# addon-candle-2.net
KiCad netlist of a schematic drawn in EAGLE
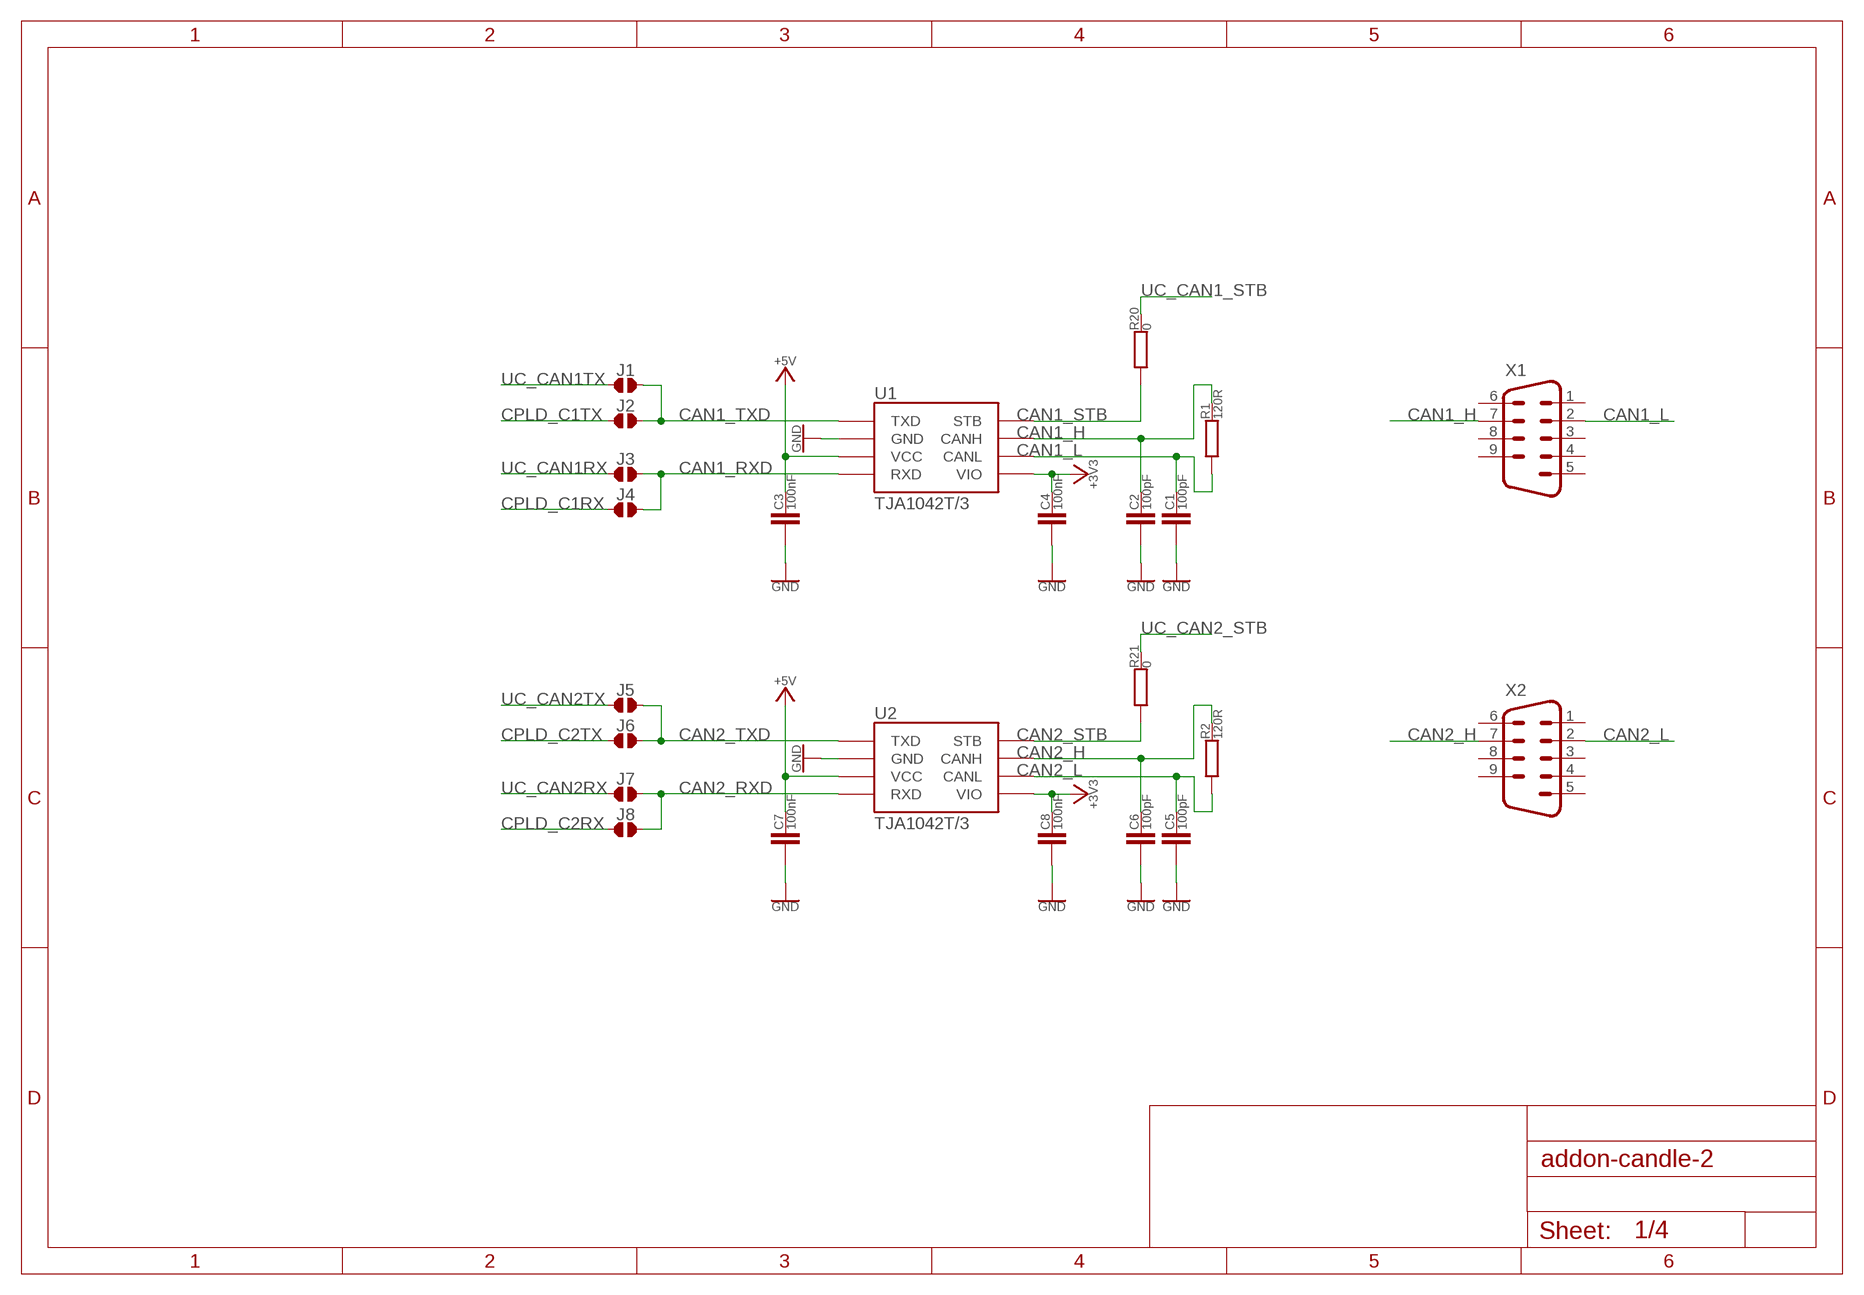
[diagram p0: schematic, sheet 1]
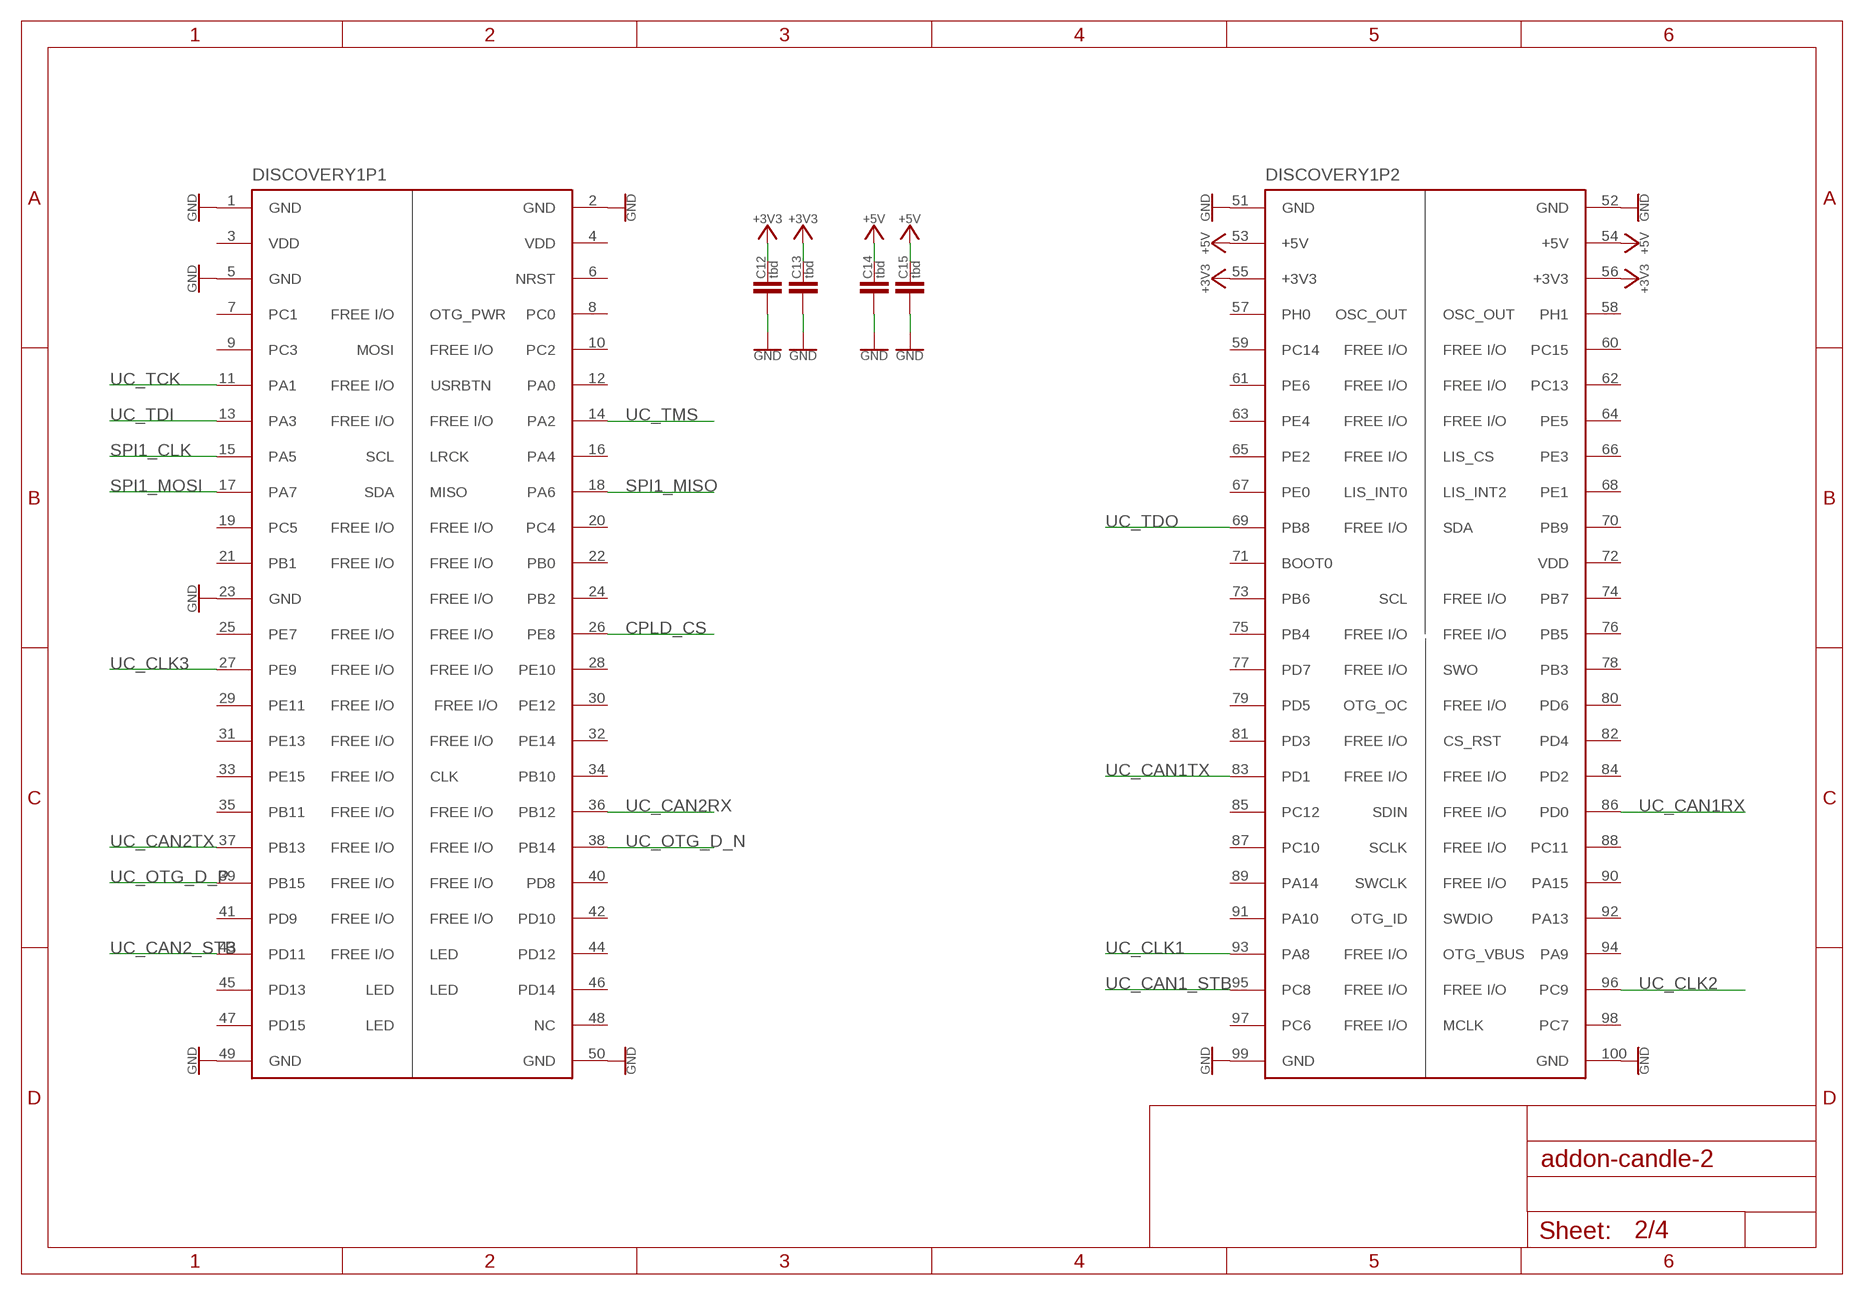
[diagram p1: schematic, sheet 2]
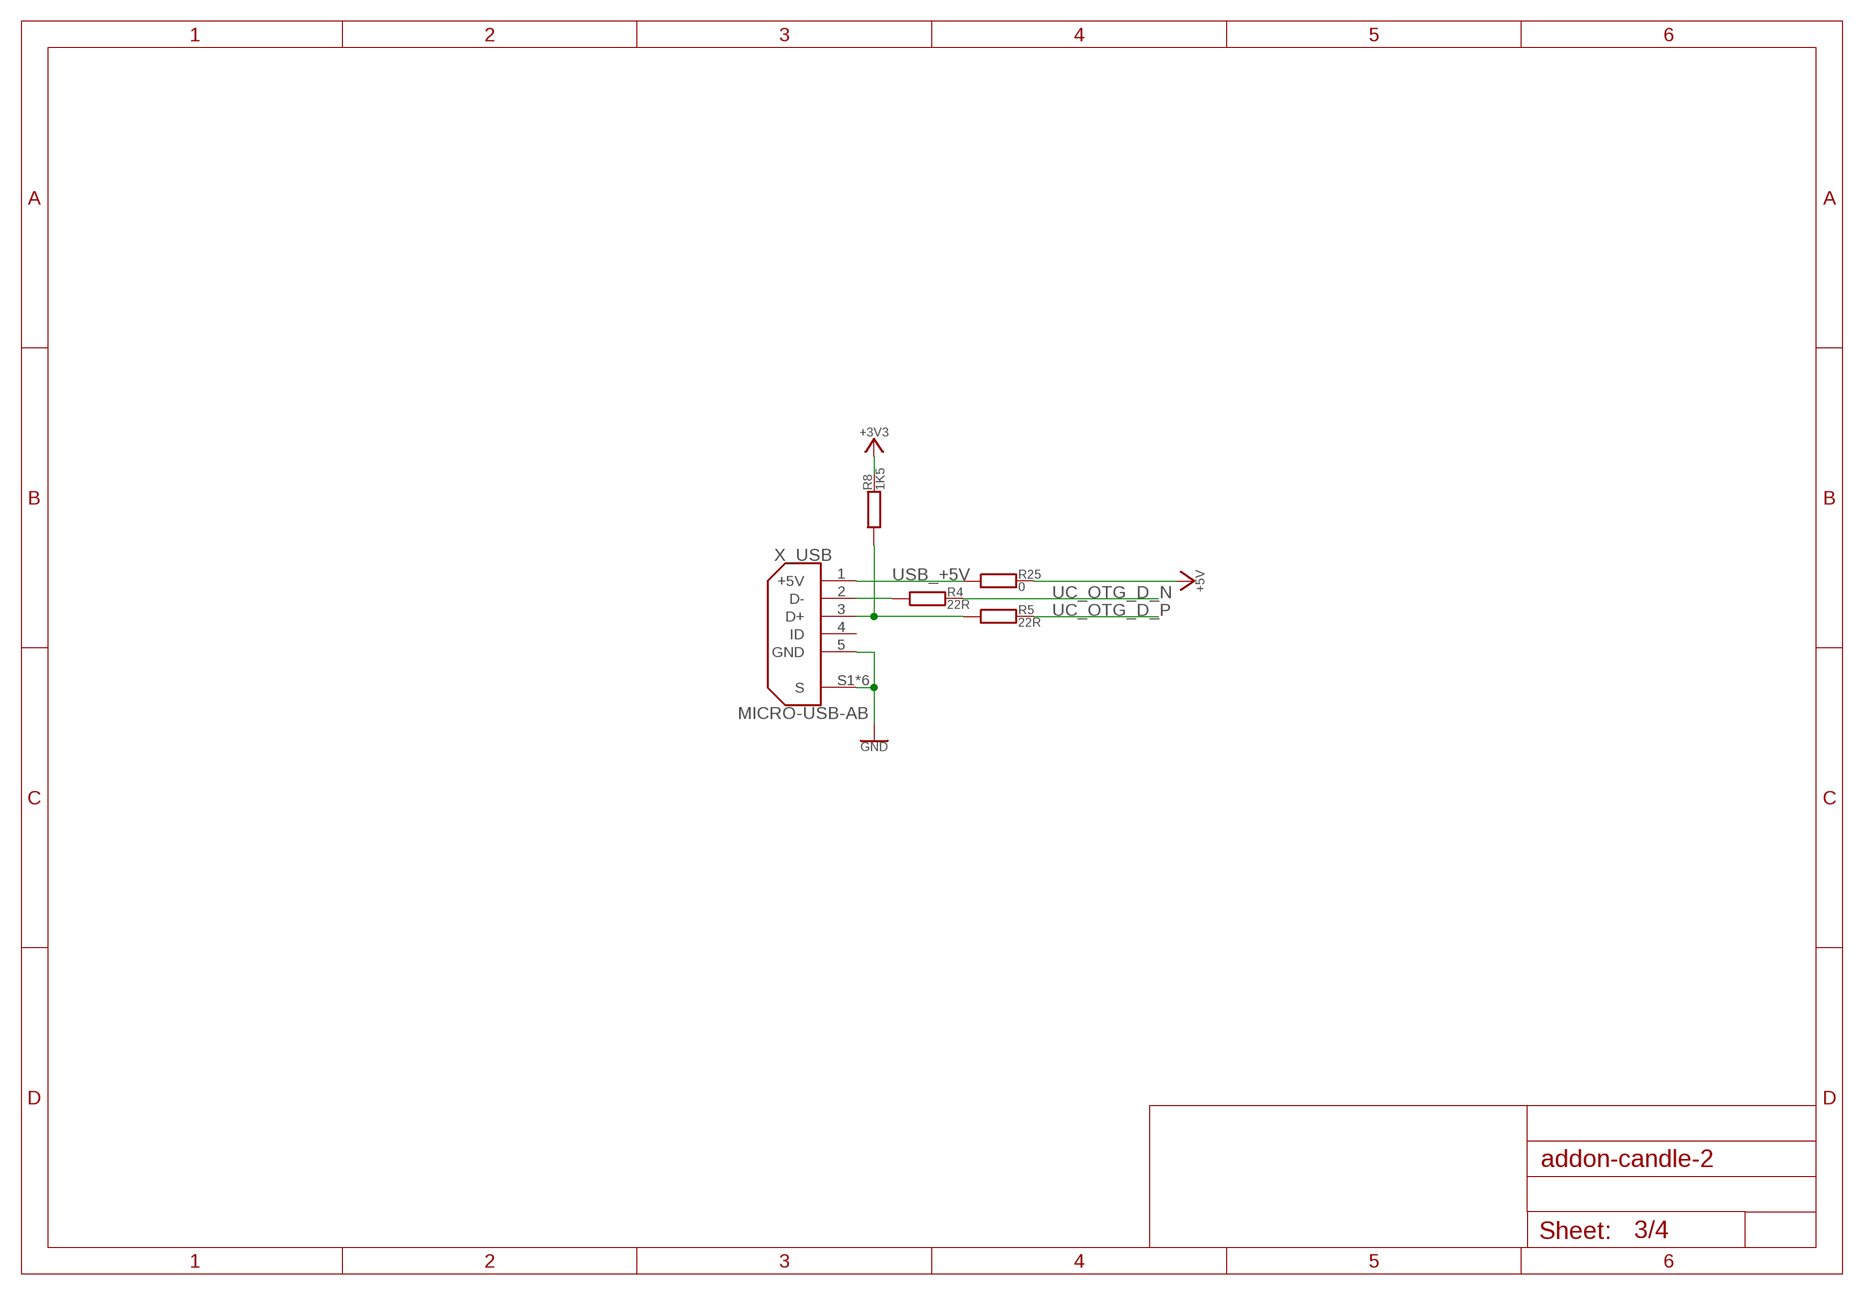
[diagram p2: schematic, sheet 3]
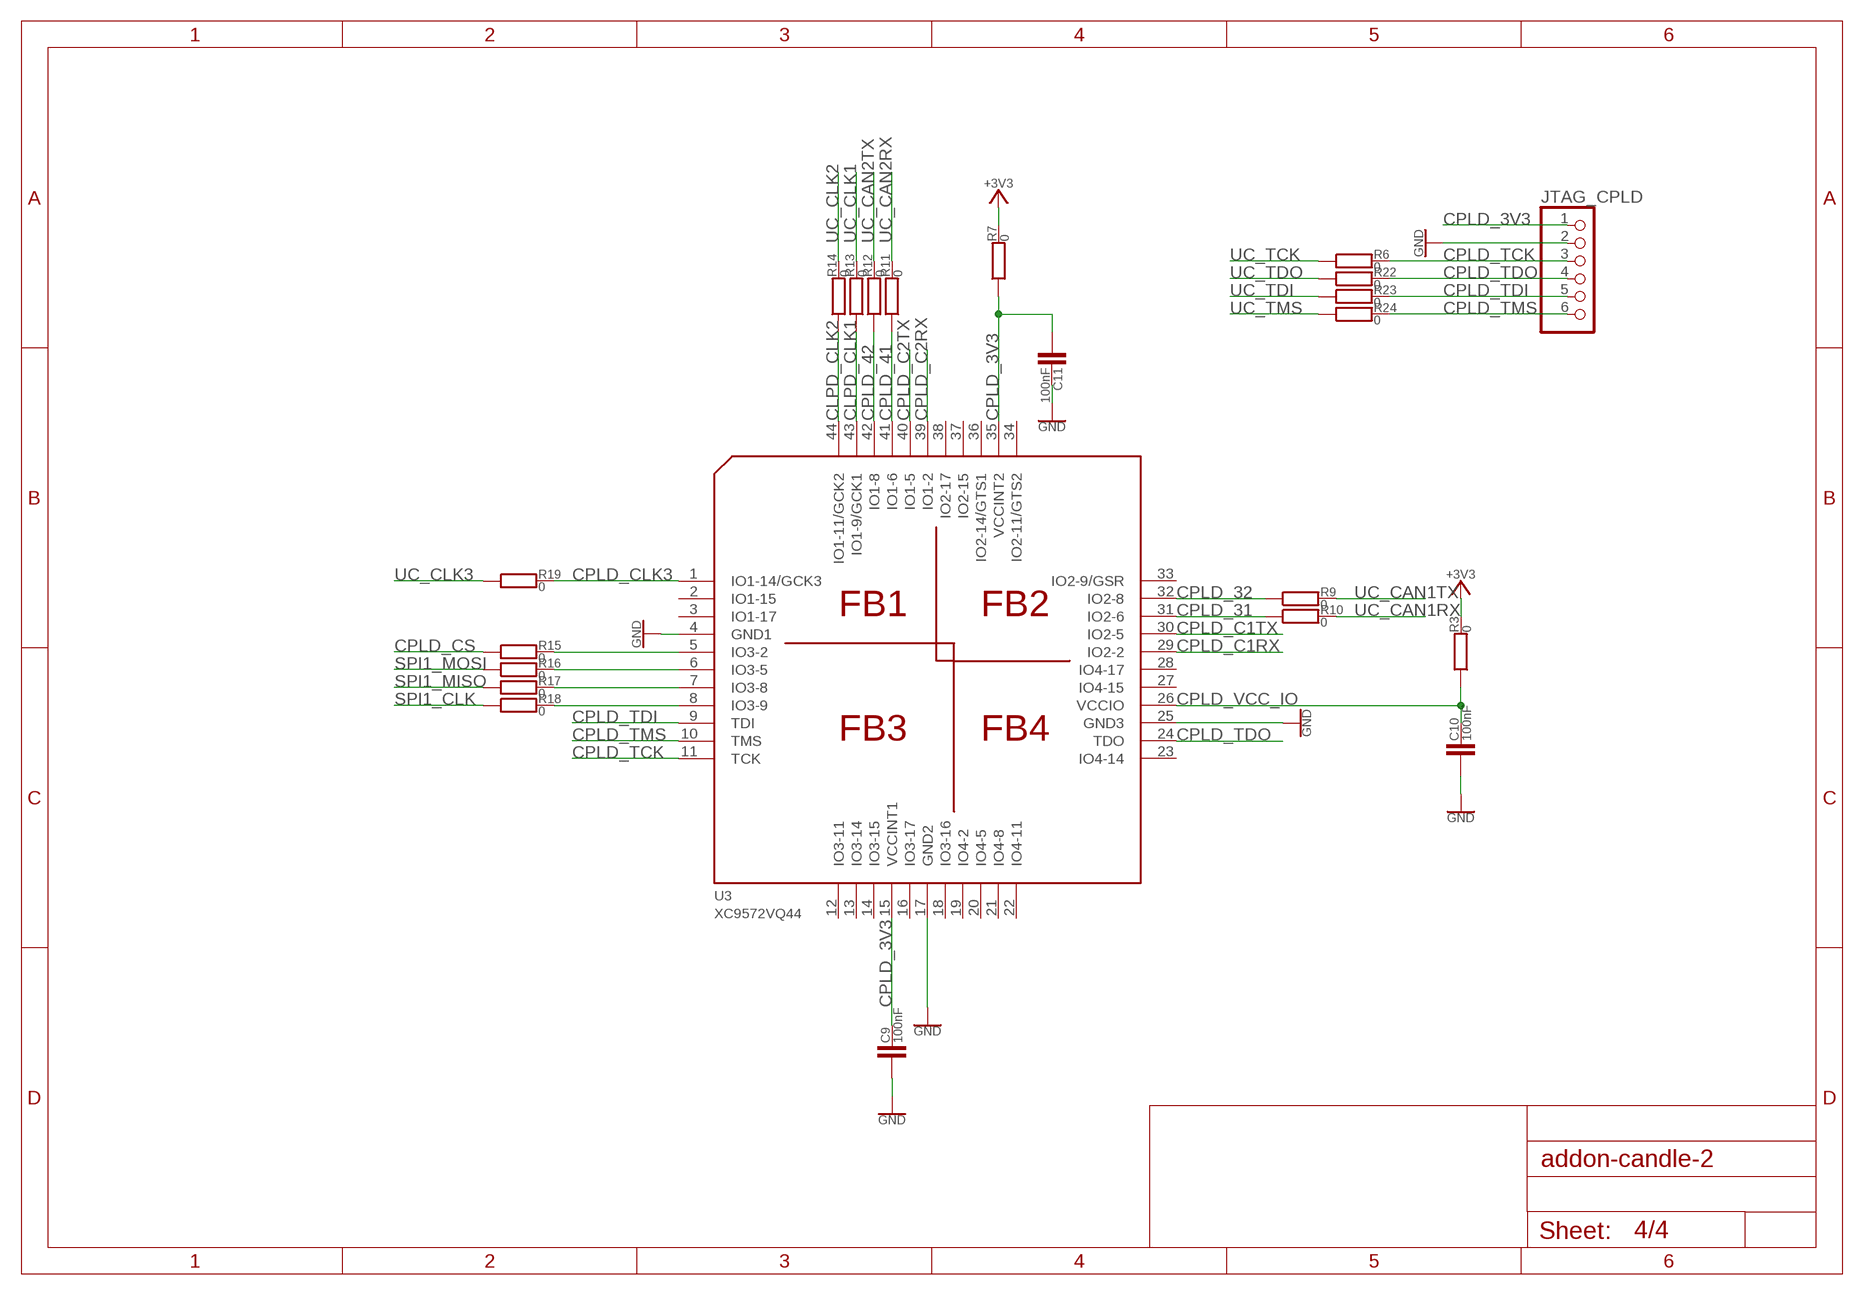
[diagram p3: schematic, sheet 4]

(export (version "E")
  (design (tool "Eeschema 10.0.6"))
  (components
    (comp (ref "C12")
      (value "tbd")
      (footprint "eagle-import:C1206")
      (libsource (lib "eagle-import") (part "C1206"))
    )
    (comp (ref "C13")
      (value "tbd")
      (footprint "eagle-import:C1206")
      (libsource (lib "eagle-import") (part "C1206"))
    )
    (comp (ref "C14")
      (value "tbd")
      (footprint "eagle-import:C1206")
      (libsource (lib "eagle-import") (part "C1206"))
    )
    (comp (ref "C15")
      (value "tbd")
      (footprint "eagle-import:C1206")
      (libsource (lib "eagle-import") (part "C1206"))
    )
    (comp (ref "DISCOVERY1")
      (value "STM32F4DISCOVERY")
      (footprint "eagle-import:STM32F4DISCOVERY")
      (libsource (lib "eagle-import") (part "STM32F4DISCOVERY"))
    )
    (comp (ref "C1")
      (value "100pF")
      (footprint "eagle-import:C0603")
      (libsource (lib "eagle-import") (part "C0603"))
    )
    (comp (ref "C2")
      (value "100pF")
      (footprint "eagle-import:C0603")
      (libsource (lib "eagle-import") (part "C0603"))
    )
    (comp (ref "C3")
      (value "100nF")
      (footprint "eagle-import:C0603")
      (libsource (lib "eagle-import") (part "C0603"))
    )
    (comp (ref "C4")
      (value "100nF")
      (footprint "eagle-import:C0603")
      (libsource (lib "eagle-import") (part "C0603"))
    )
    (comp (ref "C5")
      (value "100pF")
      (footprint "eagle-import:C0603")
      (libsource (lib "eagle-import") (part "C0603"))
    )
    (comp (ref "C6")
      (value "100pF")
      (footprint "eagle-import:C0603")
      (libsource (lib "eagle-import") (part "C0603"))
    )
    (comp (ref "C7")
      (value "100nF")
      (footprint "eagle-import:C0603")
      (libsource (lib "eagle-import") (part "C0603"))
    )
    (comp (ref "C8")
      (value "100nF")
      (footprint "eagle-import:C0603")
      (libsource (lib "eagle-import") (part "C0603"))
    )
    (comp (ref "J1")
      (value "JUMPER-2_10B")
      (footprint "eagle-import:JMP2-1B")
      (libsource (lib "eagle-import") (part "JUMPER-2_10B"))
    )
    (comp (ref "J2")
      (value "JUMPER-2_10B")
      (footprint "eagle-import:JMP2-1B")
      (libsource (lib "eagle-import") (part "JUMPER-2_10B"))
    )
    (comp (ref "J3")
      (value "JUMPER-2_10B")
      (footprint "eagle-import:JMP2-1B")
      (libsource (lib "eagle-import") (part "JUMPER-2_10B"))
    )
    (comp (ref "J4")
      (value "JUMPER-2_10B")
      (footprint "eagle-import:JMP2-1B")
      (libsource (lib "eagle-import") (part "JUMPER-2_10B"))
    )
    (comp (ref "J5")
      (value "JUMPER-2_10B")
      (footprint "eagle-import:JMP2-1B")
      (libsource (lib "eagle-import") (part "JUMPER-2_10B"))
    )
    (comp (ref "J6")
      (value "JUMPER-2_10B")
      (footprint "eagle-import:JMP2-1B")
      (libsource (lib "eagle-import") (part "JUMPER-2_10B"))
    )
    (comp (ref "J7")
      (value "JUMPER-2_10B")
      (footprint "eagle-import:JMP2-1B")
      (libsource (lib "eagle-import") (part "JUMPER-2_10B"))
    )
    (comp (ref "J8")
      (value "JUMPER-2_10B")
      (footprint "eagle-import:JMP2-1B")
      (libsource (lib "eagle-import") (part "JUMPER-2_10B"))
    )
    (comp (ref "R1")
      (value "120R")
      (footprint "eagle-import:R0603")
      (libsource (lib "eagle-import") (part "R0603"))
    )
    (comp (ref "R2")
      (value "120R")
      (footprint "eagle-import:R0603")
      (libsource (lib "eagle-import") (part "R0603"))
    )
    (comp (ref "R20")
      (value "0")
      (footprint "eagle-import:R0603")
      (libsource (lib "eagle-import") (part "R0603"))
    )
    (comp (ref "R21")
      (value "0")
      (footprint "eagle-import:R0603")
      (libsource (lib "eagle-import") (part "R0603"))
    )
    (comp (ref "U1")
      (value "TJA1042T/3")
      (footprint "eagle-import:SO08")
      (libsource (lib "eagle-import") (part "TJA1042T/3"))
    )
    (comp (ref "U2")
      (value "TJA1042T/3")
      (footprint "eagle-import:SO08")
      (libsource (lib "eagle-import") (part "TJA1042T/3"))
    )
    (comp (ref "X1")
      (value "M09-182")
      (footprint "eagle-import:182-009-MALE")
      (libsource (lib "eagle-import") (part "M09-182"))
    )
    (comp (ref "X2")
      (value "M09-182")
      (footprint "eagle-import:182-009-MALE")
      (libsource (lib "eagle-import") (part "M09-182"))
    )
    (comp (ref "C9")
      (value "100nF")
      (footprint "eagle-import:C0603")
      (libsource (lib "eagle-import") (part "C0603"))
    )
    (comp (ref "C10")
      (value "100nF")
      (footprint "eagle-import:C0603")
      (libsource (lib "eagle-import") (part "C0603"))
    )
    (comp (ref "C11")
      (value "100nF")
      (footprint "eagle-import:C0603")
      (libsource (lib "eagle-import") (part "C0603"))
    )
    (comp (ref "JTAG_CPLD")
      (value "PINHD-1X6")
      (footprint "eagle-import:1X06")
      (libsource (lib "eagle-import") (part "PINHD-1X6"))
    )
    (comp (ref "R3")
      (value "0")
      (footprint "eagle-import:R0603")
      (libsource (lib "eagle-import") (part "R0603"))
    )
    (comp (ref "R6")
      (value "0")
      (footprint "eagle-import:R0603")
      (libsource (lib "eagle-import") (part "R0603"))
    )
    (comp (ref "R7")
      (value "0")
      (footprint "eagle-import:R0603")
      (libsource (lib "eagle-import") (part "R0603"))
    )
    (comp (ref "R9")
      (value "0")
      (footprint "eagle-import:R0603")
      (libsource (lib "eagle-import") (part "R0603"))
    )
    (comp (ref "R10")
      (value "0")
      (footprint "eagle-import:R0603")
      (libsource (lib "eagle-import") (part "R0603"))
    )
    (comp (ref "R11")
      (value "0")
      (footprint "eagle-import:R0603")
      (libsource (lib "eagle-import") (part "R0603"))
    )
    (comp (ref "R12")
      (value "0")
      (footprint "eagle-import:R0603")
      (libsource (lib "eagle-import") (part "R0603"))
    )
    (comp (ref "R13")
      (value "0")
      (footprint "eagle-import:R0603")
      (libsource (lib "eagle-import") (part "R0603"))
    )
    (comp (ref "R14")
      (value "0")
      (footprint "eagle-import:R0603")
      (libsource (lib "eagle-import") (part "R0603"))
    )
    (comp (ref "R15")
      (value "0")
      (footprint "eagle-import:R0603")
      (libsource (lib "eagle-import") (part "R0603"))
    )
    (comp (ref "R16")
      (value "0")
      (footprint "eagle-import:R0603")
      (libsource (lib "eagle-import") (part "R0603"))
    )
    (comp (ref "R17")
      (value "0")
      (footprint "eagle-import:R0603")
      (libsource (lib "eagle-import") (part "R0603"))
    )
    (comp (ref "R18")
      (value "0")
      (footprint "eagle-import:R0603")
      (libsource (lib "eagle-import") (part "R0603"))
    )
    (comp (ref "R19")
      (value "0")
      (footprint "eagle-import:R0603")
      (libsource (lib "eagle-import") (part "R0603"))
    )
    (comp (ref "R22")
      (value "0")
      (footprint "eagle-import:R0603")
      (libsource (lib "eagle-import") (part "R0603"))
    )
    (comp (ref "R23")
      (value "0")
      (footprint "eagle-import:R0603")
      (libsource (lib "eagle-import") (part "R0603"))
    )
    (comp (ref "R24")
      (value "0")
      (footprint "eagle-import:R0603")
      (libsource (lib "eagle-import") (part "R0603"))
    )
    (comp (ref "U3")
      (value "XC9572VQ44")
      (footprint "eagle-import:VQ44")
      (libsource (lib "eagle-import") (part "XC9572VQ44"))
    )
    (comp (ref "R4")
      (value "22R")
      (footprint "eagle-import:R0603")
      (libsource (lib "eagle-import") (part "R0603"))
    )
    (comp (ref "R5")
      (value "22R")
      (footprint "eagle-import:R0603")
      (libsource (lib "eagle-import") (part "R0603"))
    )
    (comp (ref "R8")
      (value "1K5")
      (footprint "eagle-import:R0603")
      (libsource (lib "eagle-import") (part "R0603"))
    )
    (comp (ref "R25")
      (value "0")
      (footprint "eagle-import:R0603")
      (libsource (lib "eagle-import") (part "R0603"))
    )
    (comp (ref "X_USB")
      (value "MICRO-USB-AB")
      (footprint "eagle-import:ZX62-B-5PA(11)")
      (fields (field (name "MF") "HIROSE") (field (name "MPN") "ZX62-AB-5PA(11)"))
      (libsource (lib "eagle-import") (part "MICRO-USB-AB"))
    )
  )
  (nets
    (net (code "1") (name "+3V3") (class "Default")
      (node (ref "C12") (pin "2") (pinfunction "2_2") (pintype "passive"))
      (node (ref "C13") (pin "2") (pinfunction "2_2") (pintype "passive"))
      (node (ref "C4") (pin "2") (pinfunction "2_2") (pintype "passive"))
      (node (ref "C8") (pin "2") (pinfunction "2_2") (pintype "passive"))
      (node (ref "DISCOVERY1") (pin "55") (pinfunction "+3V3_55") (pintype "bidirectional"))
      (node (ref "DISCOVERY1") (pin "56") (pinfunction "+3V3_56") (pintype "bidirectional"))
      (node (ref "R3") (pin "2") (pinfunction "2_2") (pintype "passive"))
      (node (ref "R7") (pin "2") (pinfunction "2_2") (pintype "passive"))
      (node (ref "R8") (pin "2") (pinfunction "2_2") (pintype "passive"))
      (node (ref "U1") (pin "5") (pinfunction "VIO_5") (pintype "passive"))
      (node (ref "U2") (pin "5") (pinfunction "VIO_5") (pintype "passive"))
    )
    (net (code "2") (name "+5V") (class "Default")
      (node (ref "C14") (pin "2") (pinfunction "2_2") (pintype "passive"))
      (node (ref "C15") (pin "2") (pinfunction "2_2") (pintype "passive"))
      (node (ref "C3") (pin "2") (pinfunction "2_2") (pintype "passive"))
      (node (ref "C7") (pin "2") (pinfunction "2_2") (pintype "passive"))
      (node (ref "DISCOVERY1") (pin "53") (pinfunction "+5V_53") (pintype "bidirectional"))
      (node (ref "DISCOVERY1") (pin "54") (pinfunction "+5V_54") (pintype "bidirectional"))
      (node (ref "R25") (pin "2") (pinfunction "2_2") (pintype "passive"))
      (node (ref "U1") (pin "3") (pinfunction "VCC_3") (pintype "power_in"))
      (node (ref "U2") (pin "3") (pinfunction "VCC_3") (pintype "power_in"))
    )
    (net (code "3") (name "CAN1_H") (class "Default")
      (node (ref "C2") (pin "2") (pinfunction "2_2") (pintype "passive"))
      (node (ref "R1") (pin "2") (pinfunction "2_2") (pintype "passive"))
      (node (ref "U1") (pin "7") (pinfunction "CANH_7") (pintype "passive"))
      (node (ref "X1") (pin "7") (pinfunction "7_7") (pintype "passive"))
    )
    (net (code "4") (name "CAN1_L") (class "Default")
      (node (ref "C1") (pin "2") (pinfunction "2_2") (pintype "passive"))
      (node (ref "R1") (pin "1") (pinfunction "1_1") (pintype "passive"))
      (node (ref "U1") (pin "6") (pinfunction "CANL_6") (pintype "passive"))
      (node (ref "X1") (pin "2") (pinfunction "2_2") (pintype "passive"))
    )
    (net (code "5") (name "CAN1_RXD") (class "Default")
      (node (ref "J3") (pin "1") (pinfunction "1_1") (pintype "passive"))
      (node (ref "J4") (pin "1") (pinfunction "1_1") (pintype "passive"))
      (node (ref "U1") (pin "4") (pinfunction "RXD_4") (pintype "output"))
    )
    (net (code "6") (name "CAN1_STB") (class "Default")
      (node (ref "R20") (pin "1") (pinfunction "1_1") (pintype "passive"))
      (node (ref "U1") (pin "8") (pinfunction "STB_8") (pintype "input"))
    )
    (net (code "7") (name "CAN1_TXD") (class "Default")
      (node (ref "J1") (pin "1") (pinfunction "1_1") (pintype "passive"))
      (node (ref "J2") (pin "1") (pinfunction "1_1") (pintype "passive"))
      (node (ref "U1") (pin "1") (pinfunction "TXD_1") (pintype "input"))
    )
    (net (code "8") (name "CAN2_H") (class "Default")
      (node (ref "C6") (pin "2") (pinfunction "2_2") (pintype "passive"))
      (node (ref "R2") (pin "2") (pinfunction "2_2") (pintype "passive"))
      (node (ref "U2") (pin "7") (pinfunction "CANH_7") (pintype "passive"))
      (node (ref "X2") (pin "7") (pinfunction "7_7") (pintype "passive"))
    )
    (net (code "9") (name "CAN2_L") (class "Default")
      (node (ref "C5") (pin "2") (pinfunction "2_2") (pintype "passive"))
      (node (ref "R2") (pin "1") (pinfunction "1_1") (pintype "passive"))
      (node (ref "U2") (pin "6") (pinfunction "CANL_6") (pintype "passive"))
      (node (ref "X2") (pin "2") (pinfunction "2_2") (pintype "passive"))
    )
    (net (code "10") (name "CAN2_RXD") (class "Default")
      (node (ref "J7") (pin "1") (pinfunction "1_1") (pintype "passive"))
      (node (ref "J8") (pin "1") (pinfunction "1_1") (pintype "passive"))
      (node (ref "U2") (pin "4") (pinfunction "RXD_4") (pintype "output"))
    )
    (net (code "11") (name "CAN2_STB") (class "Default")
      (node (ref "R21") (pin "1") (pinfunction "1_1") (pintype "passive"))
      (node (ref "U2") (pin "8") (pinfunction "STB_8") (pintype "input"))
    )
    (net (code "12") (name "CAN2_TXD") (class "Default")
      (node (ref "J5") (pin "1") (pinfunction "1_1") (pintype "passive"))
      (node (ref "J6") (pin "1") (pinfunction "1_1") (pintype "passive"))
      (node (ref "U2") (pin "1") (pinfunction "TXD_1") (pintype "input"))
    )
    (net (code "13") (name "CLPD_CLK1") (class "Default")
      (node (ref "R13") (pin "1") (pinfunction "1_1") (pintype "passive"))
      (node (ref "U3") (pin "43") (pinfunction "IO1-9/GCK1_43") (pintype "bidirectional"))
    )
    (net (code "14") (name "CLPD_CLK2") (class "Default")
      (node (ref "R14") (pin "1") (pinfunction "1_1") (pintype "passive"))
      (node (ref "U3") (pin "44") (pinfunction "IO1-11/GCK2_44") (pintype "bidirectional"))
    )
    (net (code "15") (name "CPLD_3V3") (class "Default")
      (node (ref "C11") (pin "1") (pinfunction "1_1") (pintype "passive"))
      (node (ref "C9") (pin "2") (pinfunction "2_2") (pintype "passive"))
      (node (ref "JTAG_CPLD") (pin "1") (pinfunction "1_1") (pintype "passive"))
      (node (ref "R7") (pin "1") (pinfunction "1_1") (pintype "passive"))
      (node (ref "U3") (pin "15") (pinfunction "VCCINT1_15") (pintype "bidirectional"))
      (node (ref "U3") (pin "35") (pinfunction "VCCINT2_35") (pintype "bidirectional"))
    )
    (net (code "16") (name "CPLD_31") (class "Default")
      (node (ref "R10") (pin "1") (pinfunction "1_1") (pintype "passive"))
      (node (ref "U3") (pin "31") (pinfunction "IO2-6_31") (pintype "bidirectional"))
    )
    (net (code "17") (name "CPLD_32") (class "Default")
      (node (ref "R9") (pin "1") (pinfunction "1_1") (pintype "passive"))
      (node (ref "U3") (pin "32") (pinfunction "IO2-8_32") (pintype "bidirectional"))
    )
    (net (code "18") (name "CPLD_41") (class "Default")
      (node (ref "R11") (pin "1") (pinfunction "1_1") (pintype "passive"))
      (node (ref "U3") (pin "41") (pinfunction "IO1-6_41") (pintype "bidirectional"))
    )
    (net (code "19") (name "CPLD_42") (class "Default")
      (node (ref "R12") (pin "1") (pinfunction "1_1") (pintype "passive"))
      (node (ref "U3") (pin "42") (pinfunction "IO1-8_42") (pintype "bidirectional"))
    )
    (net (code "20") (name "CPLD_C1RX") (class "Default")
      (node (ref "J4") (pin "2") (pinfunction "2_2") (pintype "passive"))
      (node (ref "U3") (pin "29") (pinfunction "IO2-2_29") (pintype "bidirectional"))
    )
    (net (code "21") (name "CPLD_C1TX") (class "Default")
      (node (ref "J2") (pin "2") (pinfunction "2_2") (pintype "passive"))
      (node (ref "U3") (pin "30") (pinfunction "IO2-5_30") (pintype "bidirectional"))
    )
    (net (code "22") (name "CPLD_C2RX") (class "Default")
      (node (ref "J8") (pin "2") (pinfunction "2_2") (pintype "passive"))
      (node (ref "U3") (pin "39") (pinfunction "IO1-2_39") (pintype "bidirectional"))
    )
    (net (code "23") (name "CPLD_C2TX") (class "Default")
      (node (ref "J6") (pin "2") (pinfunction "2_2") (pintype "passive"))
      (node (ref "U3") (pin "40") (pinfunction "IO1-5_40") (pintype "bidirectional"))
    )
    (net (code "24") (name "CPLD_CLK3") (class "Default")
      (node (ref "R19") (pin "2") (pinfunction "2_2") (pintype "passive"))
      (node (ref "U3") (pin "1") (pinfunction "IO1-14/GCK3_1") (pintype "bidirectional"))
    )
    (net (code "25") (name "CPLD_CS") (class "Default")
      (node (ref "DISCOVERY1") (pin "26") (pinfunction "PE8_26") (pintype "bidirectional"))
      (node (ref "R15") (pin "1") (pinfunction "1_1") (pintype "passive"))
    )
    (net (code "26") (name "CPLD_TCK") (class "Default")
      (node (ref "JTAG_CPLD") (pin "3") (pinfunction "3_3") (pintype "passive"))
      (node (ref "R6") (pin "2") (pinfunction "2_2") (pintype "passive"))
      (node (ref "U3") (pin "11") (pinfunction "TCK_11") (pintype "bidirectional"))
    )
    (net (code "27") (name "CPLD_TDI") (class "Default")
      (node (ref "JTAG_CPLD") (pin "5") (pinfunction "5_5") (pintype "passive"))
      (node (ref "R23") (pin "2") (pinfunction "2_2") (pintype "passive"))
      (node (ref "U3") (pin "9") (pinfunction "TDI_9") (pintype "bidirectional"))
    )
    (net (code "28") (name "CPLD_TDO") (class "Default")
      (node (ref "JTAG_CPLD") (pin "4") (pinfunction "4_4") (pintype "passive"))
      (node (ref "R22") (pin "2") (pinfunction "2_2") (pintype "passive"))
      (node (ref "U3") (pin "24") (pinfunction "TDO_24") (pintype "bidirectional"))
    )
    (net (code "29") (name "CPLD_TMS") (class "Default")
      (node (ref "JTAG_CPLD") (pin "6") (pinfunction "6_6") (pintype "passive"))
      (node (ref "R24") (pin "2") (pinfunction "2_2") (pintype "passive"))
      (node (ref "U3") (pin "10") (pinfunction "TMS_10") (pintype "bidirectional"))
    )
    (net (code "30") (name "CPLD_VCC_IO") (class "Default")
      (node (ref "C10") (pin "2") (pinfunction "2_2") (pintype "passive"))
      (node (ref "R3") (pin "1") (pinfunction "1_1") (pintype "passive"))
      (node (ref "U3") (pin "26") (pinfunction "VCCIO_26") (pintype "bidirectional"))
    )
    (net (code "31") (name "GND") (class "Default")
      (node (ref "C1") (pin "1") (pinfunction "1_1") (pintype "passive"))
      (node (ref "C10") (pin "1") (pinfunction "1_1") (pintype "passive"))
      (node (ref "C11") (pin "2") (pinfunction "2_2") (pintype "passive"))
      (node (ref "C12") (pin "1") (pinfunction "1_1") (pintype "passive"))
      (node (ref "C13") (pin "1") (pinfunction "1_1") (pintype "passive"))
      (node (ref "C14") (pin "1") (pinfunction "1_1") (pintype "passive"))
      (node (ref "C15") (pin "1") (pinfunction "1_1") (pintype "passive"))
      (node (ref "C2") (pin "1") (pinfunction "1_1") (pintype "passive"))
      (node (ref "C3") (pin "1") (pinfunction "1_1") (pintype "passive"))
      (node (ref "C4") (pin "1") (pinfunction "1_1") (pintype "passive"))
      (node (ref "C5") (pin "1") (pinfunction "1_1") (pintype "passive"))
      (node (ref "C6") (pin "1") (pinfunction "1_1") (pintype "passive"))
      (node (ref "C7") (pin "1") (pinfunction "1_1") (pintype "passive"))
      (node (ref "C8") (pin "1") (pinfunction "1_1") (pintype "passive"))
      (node (ref "C9") (pin "1") (pinfunction "1_1") (pintype "passive"))
      (node (ref "DISCOVERY1") (pin "1") (pinfunction "GND_1") (pintype "bidirectional"))
      (node (ref "DISCOVERY1") (pin "100") (pinfunction "GND_100") (pintype "bidirectional"))
      (node (ref "DISCOVERY1") (pin "2") (pinfunction "GND_2") (pintype "bidirectional"))
      (node (ref "DISCOVERY1") (pin "23") (pinfunction "GND_23") (pintype "bidirectional"))
      (node (ref "DISCOVERY1") (pin "49") (pinfunction "GND_49") (pintype "bidirectional"))
      (node (ref "DISCOVERY1") (pin "5") (pinfunction "GND_5") (pintype "bidirectional"))
      (node (ref "DISCOVERY1") (pin "50") (pinfunction "GND_50") (pintype "bidirectional"))
      (node (ref "DISCOVERY1") (pin "51") (pinfunction "GND_51") (pintype "bidirectional"))
      (node (ref "DISCOVERY1") (pin "52") (pinfunction "GND_52") (pintype "bidirectional"))
      (node (ref "DISCOVERY1") (pin "99") (pinfunction "GND_99") (pintype "bidirectional"))
      (node (ref "JTAG_CPLD") (pin "2") (pinfunction "2_2") (pintype "passive"))
      (node (ref "U1") (pin "2") (pinfunction "GND_2") (pintype "power_in"))
      (node (ref "U2") (pin "2") (pinfunction "GND_2") (pintype "power_in"))
      (node (ref "U3") (pin "17") (pinfunction "GND2_17") (pintype "bidirectional"))
      (node (ref "U3") (pin "25") (pinfunction "GND3_25") (pintype "bidirectional"))
      (node (ref "U3") (pin "4") (pinfunction "GND1_4") (pintype "bidirectional"))
      (node (ref "X_USB") (pin "5") (pinfunction "GND_5") (pintype "passive"))
      (node (ref "X_USB") (pin "S1") (pinfunction "S_S1") (pintype "passive"))
      (node (ref "X_USB") (pin "S2") (pinfunction "S_S2") (pintype "passive"))
      (node (ref "X_USB") (pin "S3") (pinfunction "S_S3") (pintype "passive"))
      (node (ref "X_USB") (pin "S4") (pinfunction "S_S4") (pintype "passive"))
      (node (ref "X_USB") (pin "S5") (pinfunction "S_S5") (pintype "passive"))
      (node (ref "X_USB") (pin "S6") (pinfunction "S_S6") (pintype "passive"))
    )
    (net (code "32") (name "Net-(U3-IO3-2)") (class "Default")
      (node (ref "R15") (pin "2") (pinfunction "2_2") (pintype "passive"))
      (node (ref "U3") (pin "5") (pinfunction "IO3-2_5") (pintype "bidirectional"))
    )
    (net (code "33") (name "Net-(U3-IO3-5)") (class "Default")
      (node (ref "R16") (pin "2") (pinfunction "2_2") (pintype "passive"))
      (node (ref "U3") (pin "6") (pinfunction "IO3-5_6") (pintype "bidirectional"))
    )
    (net (code "34") (name "Net-(U3-IO3-8)") (class "Default")
      (node (ref "R17") (pin "2") (pinfunction "2_2") (pintype "passive"))
      (node (ref "U3") (pin "7") (pinfunction "IO3-8_7") (pintype "bidirectional"))
    )
    (net (code "35") (name "Net-(U3-IO3-9)") (class "Default")
      (node (ref "R18") (pin "2") (pinfunction "2_2") (pintype "passive"))
      (node (ref "U3") (pin "8") (pinfunction "IO3-9_8") (pintype "bidirectional"))
    )
    (net (code "36") (name "Net-(X_USB-D+)") (class "Default")
      (node (ref "R5") (pin "1") (pinfunction "1_1") (pintype "passive"))
      (node (ref "R8") (pin "1") (pinfunction "1_1") (pintype "passive"))
      (node (ref "X_USB") (pin "3") (pinfunction "D+_3") (pintype "passive"))
    )
    (net (code "37") (name "Net-(X_USB-D-)") (class "Default")
      (node (ref "R4") (pin "1") (pinfunction "1_1") (pintype "passive"))
      (node (ref "X_USB") (pin "2") (pinfunction "D-_2") (pintype "passive"))
    )
    (net (code "38") (name "SPI1_CLK") (class "Default")
      (node (ref "DISCOVERY1") (pin "15") (pinfunction "PA5_15") (pintype "bidirectional"))
      (node (ref "R18") (pin "1") (pinfunction "1_1") (pintype "passive"))
    )
    (net (code "39") (name "SPI1_MISO") (class "Default")
      (node (ref "DISCOVERY1") (pin "18") (pinfunction "PA6_18") (pintype "bidirectional"))
      (node (ref "R17") (pin "1") (pinfunction "1_1") (pintype "passive"))
    )
    (net (code "40") (name "SPI1_MOSI") (class "Default")
      (node (ref "DISCOVERY1") (pin "17") (pinfunction "PA7_17") (pintype "bidirectional"))
      (node (ref "R16") (pin "1") (pinfunction "1_1") (pintype "passive"))
    )
    (net (code "41") (name "UC_CAN1RX") (class "Default")
      (node (ref "DISCOVERY1") (pin "86") (pinfunction "PD0_86") (pintype "bidirectional"))
      (node (ref "J3") (pin "2") (pinfunction "2_2") (pintype "passive"))
      (node (ref "R10") (pin "2") (pinfunction "2_2") (pintype "passive"))
    )
    (net (code "42") (name "UC_CAN1TX") (class "Default")
      (node (ref "DISCOVERY1") (pin "83") (pinfunction "PD1_83") (pintype "bidirectional"))
      (node (ref "J1") (pin "2") (pinfunction "2_2") (pintype "passive"))
      (node (ref "R9") (pin "2") (pinfunction "2_2") (pintype "passive"))
    )
    (net (code "43") (name "UC_CAN1_STB") (class "Default")
      (node (ref "DISCOVERY1") (pin "95") (pinfunction "PC8_95") (pintype "bidirectional"))
      (node (ref "R20") (pin "2") (pinfunction "2_2") (pintype "passive"))
    )
    (net (code "44") (name "UC_CAN2RX") (class "Default")
      (node (ref "DISCOVERY1") (pin "36") (pinfunction "PB12_36") (pintype "bidirectional"))
      (node (ref "J7") (pin "2") (pinfunction "2_2") (pintype "passive"))
      (node (ref "R11") (pin "2") (pinfunction "2_2") (pintype "passive"))
    )
    (net (code "45") (name "UC_CAN2TX") (class "Default")
      (node (ref "DISCOVERY1") (pin "37") (pinfunction "PB13_37") (pintype "bidirectional"))
      (node (ref "J5") (pin "2") (pinfunction "2_2") (pintype "passive"))
      (node (ref "R12") (pin "2") (pinfunction "2_2") (pintype "passive"))
    )
    (net (code "46") (name "UC_CAN2_STB") (class "Default")
      (node (ref "DISCOVERY1") (pin "43") (pinfunction "PD11_43") (pintype "bidirectional"))
      (node (ref "R21") (pin "2") (pinfunction "2_2") (pintype "passive"))
    )
    (net (code "47") (name "UC_CLK1") (class "Default")
      (node (ref "DISCOVERY1") (pin "93") (pinfunction "PA8_93") (pintype "bidirectional"))
      (node (ref "R13") (pin "2") (pinfunction "2_2") (pintype "passive"))
    )
    (net (code "48") (name "UC_CLK2") (class "Default")
      (node (ref "DISCOVERY1") (pin "96") (pinfunction "PC9_96") (pintype "bidirectional"))
      (node (ref "R14") (pin "2") (pinfunction "2_2") (pintype "passive"))
    )
    (net (code "49") (name "UC_CLK3") (class "Default")
      (node (ref "DISCOVERY1") (pin "27") (pinfunction "PE9_27") (pintype "bidirectional"))
      (node (ref "R19") (pin "1") (pinfunction "1_1") (pintype "passive"))
    )
    (net (code "50") (name "UC_OTG_D_N") (class "Default")
      (node (ref "DISCOVERY1") (pin "38") (pinfunction "PB14_38") (pintype "bidirectional"))
      (node (ref "R4") (pin "2") (pinfunction "2_2") (pintype "passive"))
    )
    (net (code "51") (name "UC_OTG_D_P") (class "Default")
      (node (ref "DISCOVERY1") (pin "39") (pinfunction "PB15_39") (pintype "bidirectional"))
      (node (ref "R5") (pin "2") (pinfunction "2_2") (pintype "passive"))
    )
    (net (code "52") (name "UC_TCK") (class "Default")
      (node (ref "DISCOVERY1") (pin "11") (pinfunction "PA1_11") (pintype "bidirectional"))
      (node (ref "R6") (pin "1") (pinfunction "1_1") (pintype "passive"))
    )
    (net (code "53") (name "UC_TDI") (class "Default")
      (node (ref "DISCOVERY1") (pin "13") (pinfunction "PA3_13") (pintype "bidirectional"))
      (node (ref "R23") (pin "1") (pinfunction "1_1") (pintype "passive"))
    )
    (net (code "54") (name "UC_TDO") (class "Default")
      (node (ref "DISCOVERY1") (pin "69") (pinfunction "PB8_69") (pintype "bidirectional"))
      (node (ref "R22") (pin "1") (pinfunction "1_1") (pintype "passive"))
    )
    (net (code "55") (name "UC_TMS") (class "Default")
      (node (ref "DISCOVERY1") (pin "14") (pinfunction "PA2_14") (pintype "bidirectional"))
      (node (ref "R24") (pin "1") (pinfunction "1_1") (pintype "passive"))
    )
    (net (code "56") (name "USB_+5V") (class "Default")
      (node (ref "R25") (pin "1") (pinfunction "1_1") (pintype "passive"))
      (node (ref "X_USB") (pin "1") (pinfunction "+5V_1") (pintype "passive"))
    )
    (net (code "57") (name "unconnected-(DISCOVERY1A-NC-Pad48)") (class "Default")
      (node (ref "DISCOVERY1") (pin "48") (pinfunction "NC_48") (pintype "bidirectional"))
    )
    (net (code "58") (name "unconnected-(DISCOVERY1A-NRST-Pad6)") (class "Default")
      (node (ref "DISCOVERY1") (pin "6") (pinfunction "NRST_6") (pintype "bidirectional"))
    )
    (net (code "59") (name "unconnected-(DISCOVERY1A-PA0-Pad12)") (class "Default")
      (node (ref "DISCOVERY1") (pin "12") (pinfunction "PA0_12") (pintype "bidirectional"))
    )
    (net (code "60") (name "unconnected-(DISCOVERY1A-PA4-Pad16)") (class "Default")
      (node (ref "DISCOVERY1") (pin "16") (pinfunction "PA4_16") (pintype "bidirectional"))
    )
    (net (code "61") (name "unconnected-(DISCOVERY1A-PB0-Pad22)") (class "Default")
      (node (ref "DISCOVERY1") (pin "22") (pinfunction "PB0_22") (pintype "bidirectional"))
    )
    (net (code "62") (name "unconnected-(DISCOVERY1A-PB1-Pad21)") (class "Default")
      (node (ref "DISCOVERY1") (pin "21") (pinfunction "PB1_21") (pintype "bidirectional"))
    )
    (net (code "63") (name "unconnected-(DISCOVERY1A-PB2-Pad24)") (class "Default")
      (node (ref "DISCOVERY1") (pin "24") (pinfunction "PB2_24") (pintype "bidirectional"))
    )
    (net (code "64") (name "unconnected-(DISCOVERY1A-PB10-Pad34)") (class "Default")
      (node (ref "DISCOVERY1") (pin "34") (pinfunction "PB10_34") (pintype "bidirectional"))
    )
    (net (code "65") (name "unconnected-(DISCOVERY1A-PB11-Pad35)") (class "Default")
      (node (ref "DISCOVERY1") (pin "35") (pinfunction "PB11_35") (pintype "bidirectional"))
    )
    (net (code "66") (name "unconnected-(DISCOVERY1A-PC0-Pad8)") (class "Default")
      (node (ref "DISCOVERY1") (pin "8") (pinfunction "PC0_8") (pintype "bidirectional"))
    )
    (net (code "67") (name "unconnected-(DISCOVERY1A-PC1-Pad7)") (class "Default")
      (node (ref "DISCOVERY1") (pin "7") (pinfunction "PC1_7") (pintype "bidirectional"))
    )
    (net (code "68") (name "unconnected-(DISCOVERY1A-PC2-Pad10)") (class "Default")
      (node (ref "DISCOVERY1") (pin "10") (pinfunction "PC2_10") (pintype "bidirectional"))
    )
    (net (code "69") (name "unconnected-(DISCOVERY1A-PC3-Pad9)") (class "Default")
      (node (ref "DISCOVERY1") (pin "9") (pinfunction "PC3_9") (pintype "bidirectional"))
    )
    (net (code "70") (name "unconnected-(DISCOVERY1A-PC4-Pad20)") (class "Default")
      (node (ref "DISCOVERY1") (pin "20") (pinfunction "PC4_20") (pintype "bidirectional"))
    )
    (net (code "71") (name "unconnected-(DISCOVERY1A-PC5-Pad19)") (class "Default")
      (node (ref "DISCOVERY1") (pin "19") (pinfunction "PC5_19") (pintype "bidirectional"))
    )
    (net (code "72") (name "unconnected-(DISCOVERY1A-PD8-Pad40)") (class "Default")
      (node (ref "DISCOVERY1") (pin "40") (pinfunction "PD8_40") (pintype "bidirectional"))
    )
    (net (code "73") (name "unconnected-(DISCOVERY1A-PD9-Pad41)") (class "Default")
      (node (ref "DISCOVERY1") (pin "41") (pinfunction "PD9_41") (pintype "bidirectional"))
    )
    (net (code "74") (name "unconnected-(DISCOVERY1A-PD10-Pad42)") (class "Default")
      (node (ref "DISCOVERY1") (pin "42") (pinfunction "PD10_42") (pintype "bidirectional"))
    )
    (net (code "75") (name "unconnected-(DISCOVERY1A-PD12-Pad44)") (class "Default")
      (node (ref "DISCOVERY1") (pin "44") (pinfunction "PD12_44") (pintype "bidirectional"))
    )
    (net (code "76") (name "unconnected-(DISCOVERY1A-PD13-Pad45)") (class "Default")
      (node (ref "DISCOVERY1") (pin "45") (pinfunction "PD13_45") (pintype "bidirectional"))
    )
    (net (code "77") (name "unconnected-(DISCOVERY1A-PD14-Pad46)") (class "Default")
      (node (ref "DISCOVERY1") (pin "46") (pinfunction "PD14_46") (pintype "bidirectional"))
    )
    (net (code "78") (name "unconnected-(DISCOVERY1A-PD15-Pad47)") (class "Default")
      (node (ref "DISCOVERY1") (pin "47") (pinfunction "PD15_47") (pintype "bidirectional"))
    )
    (net (code "79") (name "unconnected-(DISCOVERY1A-PE7-Pad25)") (class "Default")
      (node (ref "DISCOVERY1") (pin "25") (pinfunction "PE7_25") (pintype "bidirectional"))
    )
    (net (code "80") (name "unconnected-(DISCOVERY1A-PE10-Pad28)") (class "Default")
      (node (ref "DISCOVERY1") (pin "28") (pinfunction "PE10_28") (pintype "bidirectional"))
    )
    (net (code "81") (name "unconnected-(DISCOVERY1A-PE11-Pad29)") (class "Default")
      (node (ref "DISCOVERY1") (pin "29") (pinfunction "PE11_29") (pintype "bidirectional"))
    )
    (net (code "82") (name "unconnected-(DISCOVERY1A-PE12-Pad30)") (class "Default")
      (node (ref "DISCOVERY1") (pin "30") (pinfunction "PE12_30") (pintype "bidirectional"))
    )
    (net (code "83") (name "unconnected-(DISCOVERY1A-PE13-Pad31)") (class "Default")
      (node (ref "DISCOVERY1") (pin "31") (pinfunction "PE13_31") (pintype "bidirectional"))
    )
    (net (code "84") (name "unconnected-(DISCOVERY1A-PE14-Pad32)") (class "Default")
      (node (ref "DISCOVERY1") (pin "32") (pinfunction "PE14_32") (pintype "bidirectional"))
    )
    (net (code "85") (name "unconnected-(DISCOVERY1A-PE15-Pad33)") (class "Default")
      (node (ref "DISCOVERY1") (pin "33") (pinfunction "PE15_33") (pintype "bidirectional"))
    )
    (net (code "86") (name "unconnected-(DISCOVERY1A-VDD-Pad3)") (class "Default")
      (node (ref "DISCOVERY1") (pin "3") (pinfunction "VDD_3") (pintype "bidirectional"))
    )
    (net (code "87") (name "unconnected-(DISCOVERY1A-VDD-Pad4)") (class "Default")
      (node (ref "DISCOVERY1") (pin "4") (pinfunction "VDD_4") (pintype "bidirectional"))
    )
    (net (code "88") (name "unconnected-(DISCOVERY1B-BOOT0-Pad71)") (class "Default")
      (node (ref "DISCOVERY1") (pin "71") (pinfunction "BOOT0_71") (pintype "bidirectional"))
    )
    (net (code "89") (name "unconnected-(DISCOVERY1B-PA9-Pad94)") (class "Default")
      (node (ref "DISCOVERY1") (pin "94") (pinfunction "PA9_94") (pintype "bidirectional"))
    )
    (net (code "90") (name "unconnected-(DISCOVERY1B-PA10-Pad91)") (class "Default")
      (node (ref "DISCOVERY1") (pin "91") (pinfunction "PA10_91") (pintype "bidirectional"))
    )
    (net (code "91") (name "unconnected-(DISCOVERY1B-PA13-Pad92)") (class "Default")
      (node (ref "DISCOVERY1") (pin "92") (pinfunction "PA13_92") (pintype "bidirectional"))
    )
    (net (code "92") (name "unconnected-(DISCOVERY1B-PA14-Pad89)") (class "Default")
      (node (ref "DISCOVERY1") (pin "89") (pinfunction "PA14_89") (pintype "bidirectional"))
    )
    (net (code "93") (name "unconnected-(DISCOVERY1B-PA15-Pad90)") (class "Default")
      (node (ref "DISCOVERY1") (pin "90") (pinfunction "PA15_90") (pintype "bidirectional"))
    )
    (net (code "94") (name "unconnected-(DISCOVERY1B-PB3-Pad78)") (class "Default")
      (node (ref "DISCOVERY1") (pin "78") (pinfunction "PB3_78") (pintype "bidirectional"))
    )
    (net (code "95") (name "unconnected-(DISCOVERY1B-PB4-Pad75)") (class "Default")
      (node (ref "DISCOVERY1") (pin "75") (pinfunction "PB4_75") (pintype "bidirectional"))
    )
    (net (code "96") (name "unconnected-(DISCOVERY1B-PB5-Pad76)") (class "Default")
      (node (ref "DISCOVERY1") (pin "76") (pinfunction "PB5_76") (pintype "bidirectional"))
    )
    (net (code "97") (name "unconnected-(DISCOVERY1B-PB6-Pad73)") (class "Default")
      (node (ref "DISCOVERY1") (pin "73") (pinfunction "PB6_73") (pintype "bidirectional"))
    )
    (net (code "98") (name "unconnected-(DISCOVERY1B-PB7-Pad74)") (class "Default")
      (node (ref "DISCOVERY1") (pin "74") (pinfunction "PB7_74") (pintype "bidirectional"))
    )
    (net (code "99") (name "unconnected-(DISCOVERY1B-PB9-Pad70)") (class "Default")
      (node (ref "DISCOVERY1") (pin "70") (pinfunction "PB9_70") (pintype "bidirectional"))
    )
    (net (code "100") (name "unconnected-(DISCOVERY1B-PC6-Pad97)") (class "Default")
      (node (ref "DISCOVERY1") (pin "97") (pinfunction "PC6_97") (pintype "bidirectional"))
    )
    (net (code "101") (name "unconnected-(DISCOVERY1B-PC7-Pad98)") (class "Default")
      (node (ref "DISCOVERY1") (pin "98") (pinfunction "PC7_98") (pintype "bidirectional"))
    )
    (net (code "102") (name "unconnected-(DISCOVERY1B-PC10-Pad87)") (class "Default")
      (node (ref "DISCOVERY1") (pin "87") (pinfunction "PC10_87") (pintype "bidirectional"))
    )
    (net (code "103") (name "unconnected-(DISCOVERY1B-PC11-Pad88)") (class "Default")
      (node (ref "DISCOVERY1") (pin "88") (pinfunction "PC11_88") (pintype "bidirectional"))
    )
    (net (code "104") (name "unconnected-(DISCOVERY1B-PC12-Pad85)") (class "Default")
      (node (ref "DISCOVERY1") (pin "85") (pinfunction "PC12_85") (pintype "bidirectional"))
    )
    (net (code "105") (name "unconnected-(DISCOVERY1B-PC13-Pad62)") (class "Default")
      (node (ref "DISCOVERY1") (pin "62") (pinfunction "PC13_62") (pintype "bidirectional"))
    )
    (net (code "106") (name "unconnected-(DISCOVERY1B-PC14-Pad59)") (class "Default")
      (node (ref "DISCOVERY1") (pin "59") (pinfunction "PC14_59") (pintype "bidirectional"))
    )
    (net (code "107") (name "unconnected-(DISCOVERY1B-PC15-Pad60)") (class "Default")
      (node (ref "DISCOVERY1") (pin "60") (pinfunction "PC15_60") (pintype "bidirectional"))
    )
    (net (code "108") (name "unconnected-(DISCOVERY1B-PD2-Pad84)") (class "Default")
      (node (ref "DISCOVERY1") (pin "84") (pinfunction "PD2_84") (pintype "bidirectional"))
    )
    (net (code "109") (name "unconnected-(DISCOVERY1B-PD3-Pad81)") (class "Default")
      (node (ref "DISCOVERY1") (pin "81") (pinfunction "PD3_81") (pintype "bidirectional"))
    )
    (net (code "110") (name "unconnected-(DISCOVERY1B-PD4-Pad82)") (class "Default")
      (node (ref "DISCOVERY1") (pin "82") (pinfunction "PD4_82") (pintype "bidirectional"))
    )
    (net (code "111") (name "unconnected-(DISCOVERY1B-PD5-Pad79)") (class "Default")
      (node (ref "DISCOVERY1") (pin "79") (pinfunction "PD5_79") (pintype "bidirectional"))
    )
    (net (code "112") (name "unconnected-(DISCOVERY1B-PD6-Pad80)") (class "Default")
      (node (ref "DISCOVERY1") (pin "80") (pinfunction "PD6_80") (pintype "bidirectional"))
    )
    (net (code "113") (name "unconnected-(DISCOVERY1B-PD7-Pad77)") (class "Default")
      (node (ref "DISCOVERY1") (pin "77") (pinfunction "PD7_77") (pintype "bidirectional"))
    )
    (net (code "114") (name "unconnected-(DISCOVERY1B-PE0-Pad67)") (class "Default")
      (node (ref "DISCOVERY1") (pin "67") (pinfunction "PE0_67") (pintype "bidirectional"))
    )
    (net (code "115") (name "unconnected-(DISCOVERY1B-PE1-Pad68)") (class "Default")
      (node (ref "DISCOVERY1") (pin "68") (pinfunction "PE1_68") (pintype "bidirectional"))
    )
    (net (code "116") (name "unconnected-(DISCOVERY1B-PE2-Pad65)") (class "Default")
      (node (ref "DISCOVERY1") (pin "65") (pinfunction "PE2_65") (pintype "bidirectional"))
    )
    (net (code "117") (name "unconnected-(DISCOVERY1B-PE3-Pad66)") (class "Default")
      (node (ref "DISCOVERY1") (pin "66") (pinfunction "PE3_66") (pintype "bidirectional"))
    )
    (net (code "118") (name "unconnected-(DISCOVERY1B-PE4-Pad63)") (class "Default")
      (node (ref "DISCOVERY1") (pin "63") (pinfunction "PE4_63") (pintype "bidirectional"))
    )
    (net (code "119") (name "unconnected-(DISCOVERY1B-PE5-Pad64)") (class "Default")
      (node (ref "DISCOVERY1") (pin "64") (pinfunction "PE5_64") (pintype "bidirectional"))
    )
    (net (code "120") (name "unconnected-(DISCOVERY1B-PE6-Pad61)") (class "Default")
      (node (ref "DISCOVERY1") (pin "61") (pinfunction "PE6_61") (pintype "bidirectional"))
    )
    (net (code "121") (name "unconnected-(DISCOVERY1B-PH0-Pad57)") (class "Default")
      (node (ref "DISCOVERY1") (pin "57") (pinfunction "PH0_57") (pintype "bidirectional"))
    )
    (net (code "122") (name "unconnected-(DISCOVERY1B-PH1-Pad58)") (class "Default")
      (node (ref "DISCOVERY1") (pin "58") (pinfunction "PH1_58") (pintype "bidirectional"))
    )
    (net (code "123") (name "unconnected-(DISCOVERY1B-VDD-Pad72)") (class "Default")
      (node (ref "DISCOVERY1") (pin "72") (pinfunction "VDD_72") (pintype "bidirectional"))
    )
    (net (code "124") (name "unconnected-(U3-IO1-15-Pad2)") (class "Default")
      (node (ref "U3") (pin "2") (pinfunction "IO1-15_2") (pintype "bidirectional"))
    )
    (net (code "125") (name "unconnected-(U3-IO1-17-Pad3)") (class "Default")
      (node (ref "U3") (pin "3") (pinfunction "IO1-17_3") (pintype "bidirectional"))
    )
    (net (code "126") (name "unconnected-(U3-IO2-9{slash}GSR-Pad33)") (class "Default")
      (node (ref "U3") (pin "33") (pinfunction "IO2-9/GSR_33") (pintype "bidirectional"))
    )
    (net (code "127") (name "unconnected-(U3-IO2-11{slash}GTS2-Pad34)") (class "Default")
      (node (ref "U3") (pin "34") (pinfunction "IO2-11/GTS2_34") (pintype "bidirectional"))
    )
    (net (code "128") (name "unconnected-(U3-IO2-14{slash}GTS1-Pad36)") (class "Default")
      (node (ref "U3") (pin "36") (pinfunction "IO2-14/GTS1_36") (pintype "bidirectional"))
    )
    (net (code "129") (name "unconnected-(U3-IO2-15-Pad37)") (class "Default")
      (node (ref "U3") (pin "37") (pinfunction "IO2-15_37") (pintype "bidirectional"))
    )
    (net (code "130") (name "unconnected-(U3-IO2-17-Pad38)") (class "Default")
      (node (ref "U3") (pin "38") (pinfunction "IO2-17_38") (pintype "bidirectional"))
    )
    (net (code "131") (name "unconnected-(U3-IO3-11-Pad12)") (class "Default")
      (node (ref "U3") (pin "12") (pinfunction "IO3-11_12") (pintype "bidirectional"))
    )
    (net (code "132") (name "unconnected-(U3-IO3-14-Pad13)") (class "Default")
      (node (ref "U3") (pin "13") (pinfunction "IO3-14_13") (pintype "bidirectional"))
    )
    (net (code "133") (name "unconnected-(U3-IO3-15-Pad14)") (class "Default")
      (node (ref "U3") (pin "14") (pinfunction "IO3-15_14") (pintype "bidirectional"))
    )
    (net (code "134") (name "unconnected-(U3-IO3-16-Pad18)") (class "Default")
      (node (ref "U3") (pin "18") (pinfunction "IO3-16_18") (pintype "bidirectional"))
    )
    (net (code "135") (name "unconnected-(U3-IO3-17-Pad16)") (class "Default")
      (node (ref "U3") (pin "16") (pinfunction "IO3-17_16") (pintype "bidirectional"))
    )
    (net (code "136") (name "unconnected-(U3-IO4-2-Pad19)") (class "Default")
      (node (ref "U3") (pin "19") (pinfunction "IO4-2_19") (pintype "bidirectional"))
    )
    (net (code "137") (name "unconnected-(U3-IO4-5-Pad20)") (class "Default")
      (node (ref "U3") (pin "20") (pinfunction "IO4-5_20") (pintype "bidirectional"))
    )
    (net (code "138") (name "unconnected-(U3-IO4-8-Pad21)") (class "Default")
      (node (ref "U3") (pin "21") (pinfunction "IO4-8_21") (pintype "bidirectional"))
    )
    (net (code "139") (name "unconnected-(U3-IO4-11-Pad22)") (class "Default")
      (node (ref "U3") (pin "22") (pinfunction "IO4-11_22") (pintype "bidirectional"))
    )
    (net (code "140") (name "unconnected-(U3-IO4-14-Pad23)") (class "Default")
      (node (ref "U3") (pin "23") (pinfunction "IO4-14_23") (pintype "bidirectional"))
    )
    (net (code "141") (name "unconnected-(U3-IO4-15-Pad27)") (class "Default")
      (node (ref "U3") (pin "27") (pinfunction "IO4-15_27") (pintype "bidirectional"))
    )
    (net (code "142") (name "unconnected-(U3-IO4-17-Pad28)") (class "Default")
      (node (ref "U3") (pin "28") (pinfunction "IO4-17_28") (pintype "bidirectional"))
    )
    (net (code "143") (name "unconnected-(X1-Pad1)") (class "Default")
      (node (ref "X1") (pin "1") (pinfunction "1_1") (pintype "passive"))
    )
    (net (code "144") (name "unconnected-(X1-Pad3)") (class "Default")
      (node (ref "X1") (pin "3") (pinfunction "3_3") (pintype "passive"))
    )
    (net (code "145") (name "unconnected-(X1-Pad4)") (class "Default")
      (node (ref "X1") (pin "4") (pinfunction "4_4") (pintype "passive"))
    )
    (net (code "146") (name "unconnected-(X1-Pad5)") (class "Default")
      (node (ref "X1") (pin "5") (pinfunction "5_5") (pintype "passive"))
    )
    (net (code "147") (name "unconnected-(X1-Pad6)") (class "Default")
      (node (ref "X1") (pin "6") (pinfunction "6_6") (pintype "passive"))
    )
    (net (code "148") (name "unconnected-(X1-Pad8)") (class "Default")
      (node (ref "X1") (pin "8") (pinfunction "8_8") (pintype "passive"))
    )
    (net (code "149") (name "unconnected-(X1-Pad9)") (class "Default")
      (node (ref "X1") (pin "9") (pinfunction "9_9") (pintype "passive"))
    )
    (net (code "150") (name "unconnected-(X2-Pad1)") (class "Default")
      (node (ref "X2") (pin "1") (pinfunction "1_1") (pintype "passive"))
    )
    (net (code "151") (name "unconnected-(X2-Pad3)") (class "Default")
      (node (ref "X2") (pin "3") (pinfunction "3_3") (pintype "passive"))
    )
    (net (code "152") (name "unconnected-(X2-Pad4)") (class "Default")
      (node (ref "X2") (pin "4") (pinfunction "4_4") (pintype "passive"))
    )
    (net (code "153") (name "unconnected-(X2-Pad5)") (class "Default")
      (node (ref "X2") (pin "5") (pinfunction "5_5") (pintype "passive"))
    )
    (net (code "154") (name "unconnected-(X2-Pad6)") (class "Default")
      (node (ref "X2") (pin "6") (pinfunction "6_6") (pintype "passive"))
    )
    (net (code "155") (name "unconnected-(X2-Pad8)") (class "Default")
      (node (ref "X2") (pin "8") (pinfunction "8_8") (pintype "passive"))
    )
    (net (code "156") (name "unconnected-(X2-Pad9)") (class "Default")
      (node (ref "X2") (pin "9") (pinfunction "9_9") (pintype "passive"))
    )
    (net (code "157") (name "unconnected-(X_USB-ID-Pad4)") (class "Default")
      (node (ref "X_USB") (pin "4") (pinfunction "ID_4") (pintype "passive"))
    )
  )
)
